# PKD.net
KiCad netlist of a schematic drawn in EAGLE
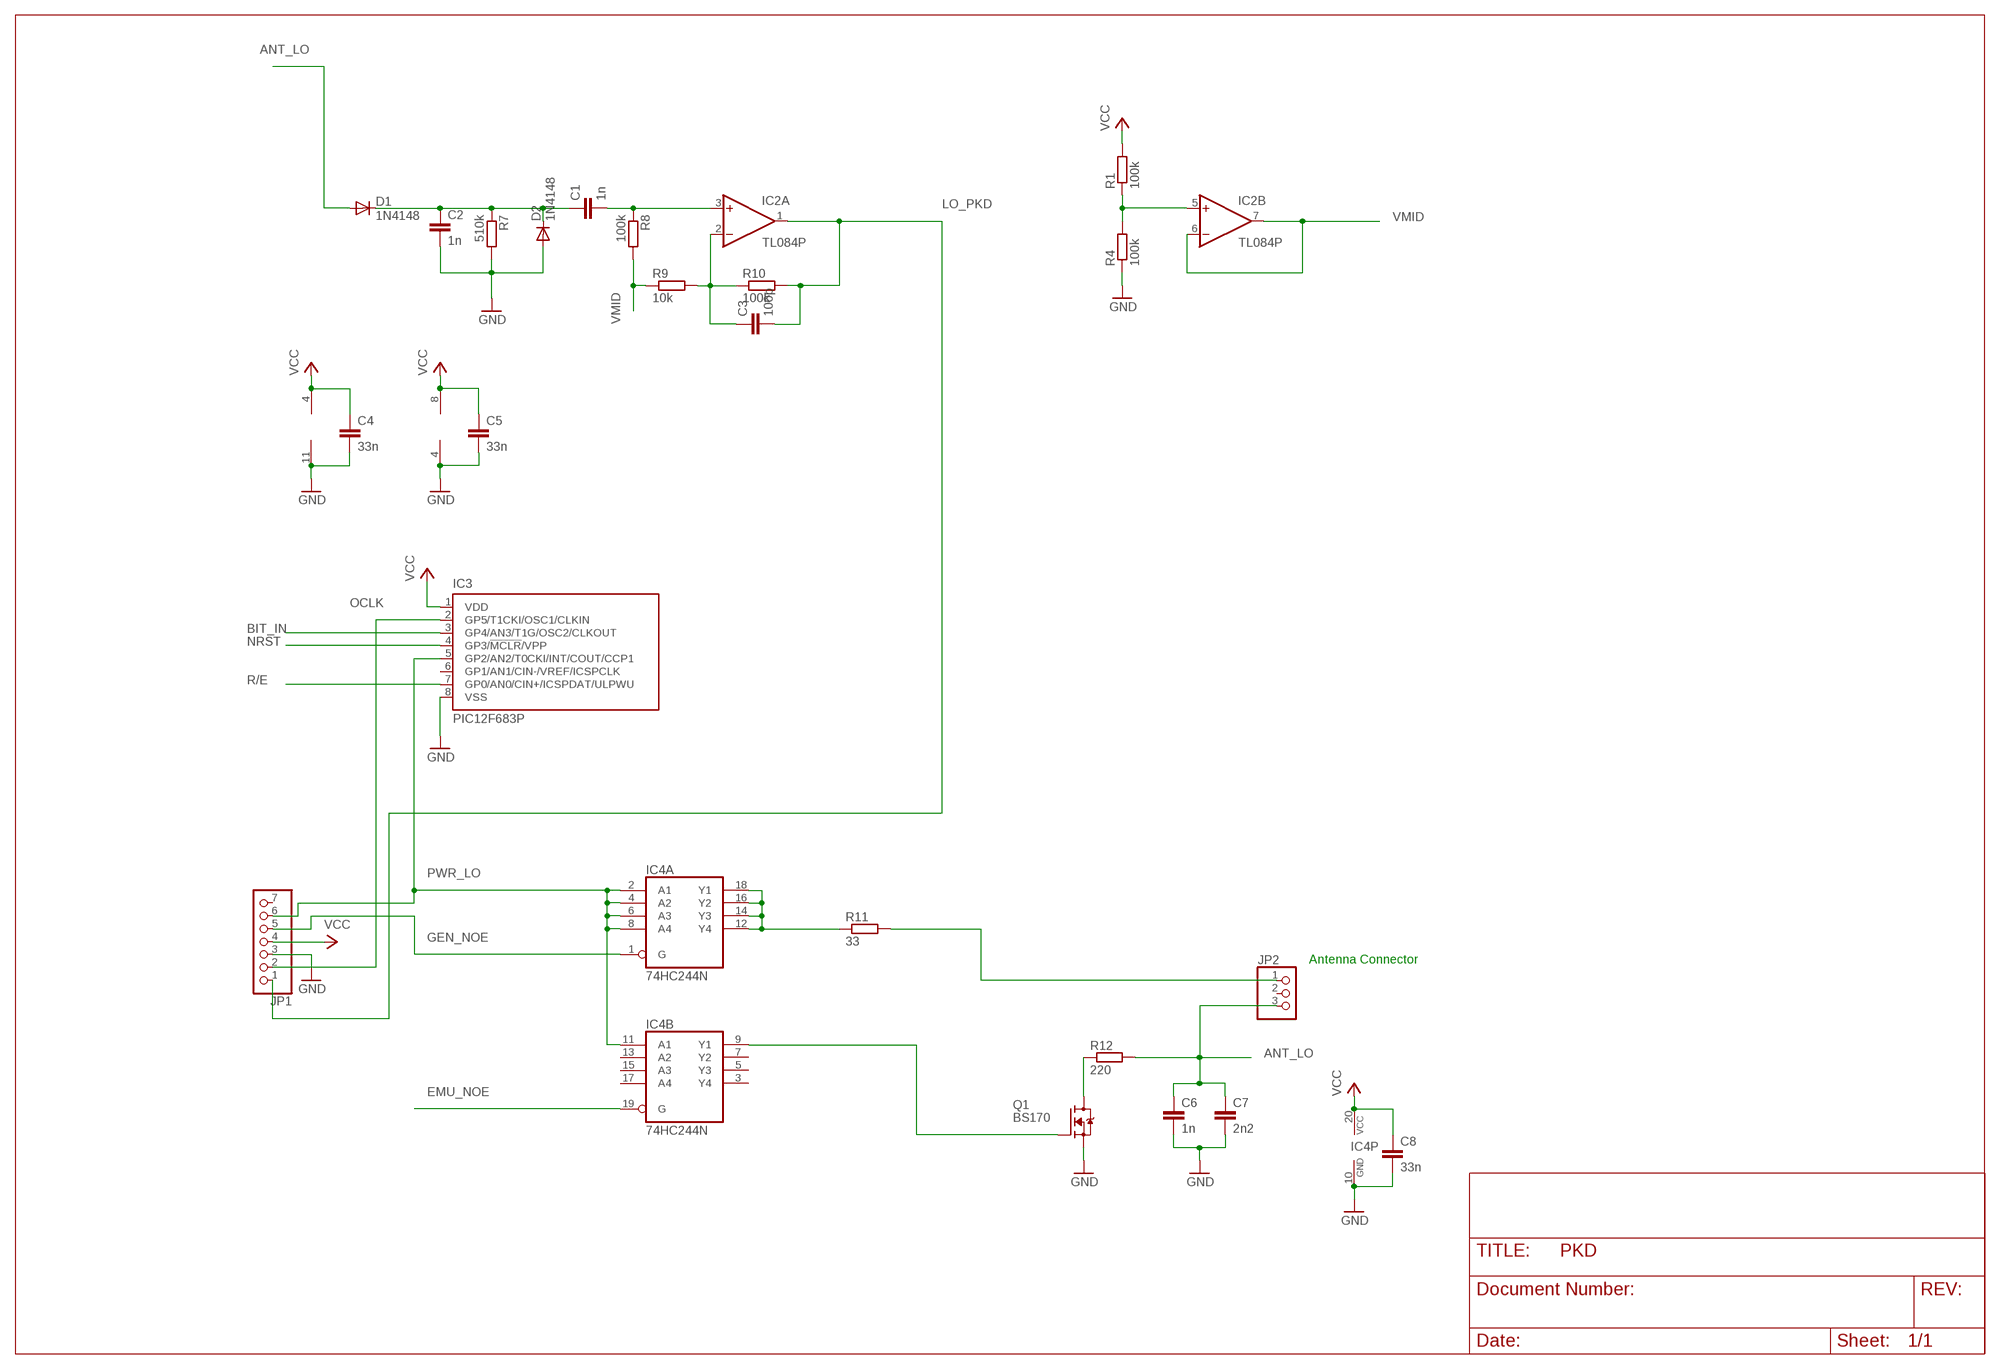
[diagram p0: schematic, sheet 1]

(export (version "E")
  (design (tool "Eeschema 10.0.6"))
  (components
    (comp (ref "C1")
      (value "1n")
      (footprint "eagle-import:C025-025X050")
      (libsource (lib "eagle-import") (part "C-EU025-025X050"))
    )
    (comp (ref "C2")
      (value "1n")
      (footprint "eagle-import:C050-030X075")
      (libsource (lib "eagle-import") (part "C-EU050-030X075"))
    )
    (comp (ref "C3")
      (value "100p")
      (footprint "eagle-import:C025-025X050")
      (libsource (lib "eagle-import") (part "C-EU025-025X050"))
    )
    (comp (ref "C4")
      (value "33n")
      (footprint "eagle-import:C025-025X050")
      (libsource (lib "eagle-import") (part "C-EU025-025X050"))
    )
    (comp (ref "C5")
      (value "33n")
      (footprint "eagle-import:C025-025X050")
      (libsource (lib "eagle-import") (part "C-EU025-025X050"))
    )
    (comp (ref "C6")
      (value "1n")
      (footprint "eagle-import:C025-025X050")
      (libsource (lib "eagle-import") (part "C-EU025-025X050"))
    )
    (comp (ref "C7")
      (value "2n2")
      (footprint "eagle-import:C025-025X050")
      (libsource (lib "eagle-import") (part "C-EU025-025X050"))
    )
    (comp (ref "C8")
      (value "33n")
      (footprint "eagle-import:C050-030X075")
      (libsource (lib "eagle-import") (part "C-EU050-030X075"))
    )
    (comp (ref "D1")
      (value "1N4148")
      (footprint "eagle-import:DO35-10")
      (libsource (lib "eagle-import") (part "1N4148DO35-10"))
    )
    (comp (ref "D2")
      (value "1N4148")
      (footprint "eagle-import:DO35-10")
      (libsource (lib "eagle-import") (part "1N4148DO35-10"))
    )
    (comp (ref "IC1")
      (value "LM393N")
      (footprint "eagle-import:DIL08")
      (libsource (lib "eagle-import") (part "LM393N"))
    )
    (comp (ref "IC2")
      (value "TL084P")
      (footprint "eagle-import:DIL14")
      (libsource (lib "eagle-import") (part "TL084P"))
    )
    (comp (ref "IC3")
      (value "PIC12F683P")
      (footprint "eagle-import:DIL8")
      (fields (field (name "MF") "MICROCHIP") (field (name "MPN") "PIC12F683-I/P"))
      (libsource (lib "eagle-import") (part "PIC12F683P"))
    )
    (comp (ref "IC4")
      (value "74HC244N")
      (footprint "eagle-import:DIL20")
      (libsource (lib "eagle-import") (part "74244NHC"))
    )
    (comp (ref "JP1")
      (value "PINHD-1X7")
      (footprint "eagle-import:1X07")
      (libsource (lib "eagle-import") (part "PINHD-1X7"))
    )
    (comp (ref "JP2")
      (value "PINHD-1X3/90")
      (footprint "eagle-import:1X03_90")
      (libsource (lib "eagle-import") (part "PINHD-1X3/90"))
    )
    (comp (ref "Q1")
      (value "BS170")
      (footprint "eagle-import:TO92-")
      (libsource (lib "eagle-import") (part "BS170"))
    )
    (comp (ref "R1")
      (value "100k")
      (footprint "eagle-import:0207_10")
      (libsource (lib "eagle-import") (part "R-EU_0207/10"))
    )
    (comp (ref "R4")
      (value "100k")
      (footprint "eagle-import:0207_10")
      (libsource (lib "eagle-import") (part "R-EU_0207/10"))
    )
    (comp (ref "R7")
      (value "510k")
      (footprint "eagle-import:0207_10")
      (libsource (lib "eagle-import") (part "R-EU_0207/10"))
    )
    (comp (ref "R8")
      (value "100k")
      (footprint "eagle-import:0207_10")
      (libsource (lib "eagle-import") (part "R-EU_0207/10"))
    )
    (comp (ref "R9")
      (value "10k")
      (footprint "eagle-import:0207_10")
      (libsource (lib "eagle-import") (part "R-EU_0207/10"))
    )
    (comp (ref "R10")
      (value "100k")
      (footprint "eagle-import:0207_10")
      (libsource (lib "eagle-import") (part "R-EU_0207/10"))
    )
    (comp (ref "R11")
      (value "33")
      (footprint "eagle-import:0207_10")
      (libsource (lib "eagle-import") (part "R-EU_0207/10"))
    )
    (comp (ref "R12")
      (value "220")
      (footprint "eagle-import:0207_10")
      (libsource (lib "eagle-import") (part "R-EU_0207/10"))
    )
  )
  (nets
    (net (code "1") (name "/ANT_LO") (class "Default")
      (node (ref "C6") (pin "1") (pinfunction "1_1") (pintype "passive"))
      (node (ref "C7") (pin "1") (pinfunction "1_1") (pintype "passive"))
      (node (ref "D1") (pin "A") (pinfunction "A_A") (pintype "passive"))
      (node (ref "JP2") (pin "3") (pinfunction "3_3") (pintype "passive"))
      (node (ref "R12") (pin "2") (pinfunction "2_2") (pintype "passive"))
    )
    (net (code "2") (name "/BIT_IN") (class "Default")
      (node (ref "IC3") (pin "3") (pinfunction "GP4/AN3/T1G/OSC2/CLKOUT_3") (pintype "bidirectional"))
    )
    (net (code "3") (name "/EMU_NOE") (class "Default")
      (node (ref "IC4") (pin "19") (pinfunction "G_19") (pintype "input"))
    )
    (net (code "4") (name "/GEN_NOE") (class "Default")
      (node (ref "IC4") (pin "1") (pinfunction "G_1") (pintype "input"))
      (node (ref "JP1") (pin "5") (pinfunction "5_5") (pintype "passive"))
    )
    (net (code "5") (name "/LO_PKD") (class "Default")
      (node (ref "C3") (pin "2") (pinfunction "2_2") (pintype "passive"))
      (node (ref "IC2") (pin "1") (pinfunction "OUT_1") (pintype "output"))
      (node (ref "JP1") (pin "1") (pinfunction "1_1") (pintype "passive"))
      (node (ref "R10") (pin "2") (pinfunction "2_2") (pintype "passive"))
    )
    (net (code "6") (name "/NRST") (class "Default")
      (node (ref "IC3") (pin "4") (pinfunction "GP3/~{MCLR}/VPP_4") (pintype "bidirectional"))
    )
    (net (code "7") (name "/OCLK") (class "Default")
      (node (ref "IC3") (pin "2") (pinfunction "GP5/T1CKI/OSC1/CLKIN_2") (pintype "bidirectional"))
      (node (ref "JP1") (pin "2") (pinfunction "2_2") (pintype "passive"))
    )
    (net (code "8") (name "/PWR_LO") (class "Default")
      (node (ref "IC3") (pin "5") (pinfunction "GP2/AN2/T0CKI/INT/COUT/CCP1_5") (pintype "bidirectional"))
      (node (ref "IC4") (pin "11") (pinfunction "A1_11") (pintype "input"))
      (node (ref "IC4") (pin "2") (pinfunction "A1_2") (pintype "input"))
      (node (ref "IC4") (pin "4") (pinfunction "A2_4") (pintype "input"))
      (node (ref "IC4") (pin "6") (pinfunction "A3_6") (pintype "input"))
      (node (ref "IC4") (pin "8") (pinfunction "A4_8") (pintype "input"))
      (node (ref "JP1") (pin "6") (pinfunction "6_6") (pintype "passive"))
    )
    (net (code "9") (name "/R{slash}E") (class "Default")
      (node (ref "IC3") (pin "7") (pinfunction "GP0/AN0/CIN+/ICSPDAT/ULPWU_7") (pintype "bidirectional"))
    )
    (net (code "10") (name "/VMID") (class "Default")
      (node (ref "IC2") (pin "6") (pinfunction "-IN_6") (pintype "input"))
      (node (ref "IC2") (pin "7") (pinfunction "OUT_7") (pintype "output"))
      (node (ref "R8") (pin "2") (pinfunction "2_2") (pintype "passive"))
      (node (ref "R9") (pin "1") (pinfunction "1_1") (pintype "passive"))
    )
    (net (code "11") (name "GND") (class "Default")
      (node (ref "C2") (pin "2") (pinfunction "2_2") (pintype "passive"))
      (node (ref "C4") (pin "2") (pinfunction "2_2") (pintype "passive"))
      (node (ref "C5") (pin "2") (pinfunction "2_2") (pintype "passive"))
      (node (ref "C6") (pin "2") (pinfunction "2_2") (pintype "passive"))
      (node (ref "C7") (pin "2") (pinfunction "2_2") (pintype "passive"))
      (node (ref "C8") (pin "2") (pinfunction "2_2") (pintype "passive"))
      (node (ref "D2") (pin "A") (pinfunction "A_A") (pintype "passive"))
      (node (ref "IC1") (pin "4") (pinfunction "V-_4") (pintype "power_in"))
      (node (ref "IC2") (pin "11") (pinfunction "V-_11") (pintype "power_in"))
      (node (ref "IC3") (pin "8") (pinfunction "VSS_8") (pintype "power_in"))
      (node (ref "IC4") (pin "10") (pinfunction "GND_10") (pintype "power_in"))
      (node (ref "JP1") (pin "3") (pinfunction "3_3") (pintype "passive"))
      (node (ref "Q1") (pin "3") (pinfunction "S_3") (pintype "passive"))
      (node (ref "R4") (pin "1") (pinfunction "1_1") (pintype "passive"))
      (node (ref "R7") (pin "2") (pinfunction "2_2") (pintype "passive"))
    )
    (net (code "12") (name "Net-(C1-Pad1)") (class "Default")
      (node (ref "C1") (pin "1") (pinfunction "1_1") (pintype "passive"))
      (node (ref "C2") (pin "1") (pinfunction "1_1") (pintype "passive"))
      (node (ref "D1") (pin "C") (pinfunction "C_C") (pintype "passive"))
      (node (ref "D2") (pin "C") (pinfunction "C_C") (pintype "passive"))
      (node (ref "R7") (pin "1") (pinfunction "1_1") (pintype "passive"))
    )
    (net (code "13") (name "Net-(IC2A-+IN)") (class "Default")
      (node (ref "C1") (pin "2") (pinfunction "2_2") (pintype "passive"))
      (node (ref "IC2") (pin "3") (pinfunction "+IN_3") (pintype "input"))
      (node (ref "R8") (pin "1") (pinfunction "1_1") (pintype "passive"))
    )
    (net (code "14") (name "Net-(IC2A--IN)") (class "Default")
      (node (ref "C3") (pin "1") (pinfunction "1_1") (pintype "passive"))
      (node (ref "IC2") (pin "2") (pinfunction "-IN_2") (pintype "input"))
      (node (ref "R10") (pin "1") (pinfunction "1_1") (pintype "passive"))
      (node (ref "R9") (pin "2") (pinfunction "2_2") (pintype "passive"))
    )
    (net (code "15") (name "Net-(IC2B-+IN)") (class "Default")
      (node (ref "IC2") (pin "5") (pinfunction "+IN_5") (pintype "input"))
      (node (ref "R1") (pin "1") (pinfunction "1_1") (pintype "passive"))
      (node (ref "R4") (pin "2") (pinfunction "2_2") (pintype "passive"))
    )
    (net (code "16") (name "Net-(IC4A-Y1)") (class "Default")
      (node (ref "IC4") (pin "12") (pinfunction "Y4_12") (pintype "tri_state"))
      (node (ref "IC4") (pin "14") (pinfunction "Y3_14") (pintype "tri_state"))
      (node (ref "IC4") (pin "16") (pinfunction "Y2_16") (pintype "tri_state"))
      (node (ref "IC4") (pin "18") (pinfunction "Y1_18") (pintype "tri_state"))
      (node (ref "R11") (pin "1") (pinfunction "1_1") (pintype "passive"))
    )
    (net (code "17") (name "Net-(IC4B-Y1)") (class "Default")
      (node (ref "IC4") (pin "9") (pinfunction "Y1_9") (pintype "tri_state"))
      (node (ref "Q1") (pin "2") (pinfunction "G_2") (pintype "passive"))
    )
    (net (code "18") (name "Net-(JP2-Pad1)") (class "Default")
      (node (ref "JP2") (pin "1") (pinfunction "1_1") (pintype "passive"))
      (node (ref "R11") (pin "2") (pinfunction "2_2") (pintype "passive"))
    )
    (net (code "19") (name "Net-(Q1-D)") (class "Default")
      (node (ref "Q1") (pin "1") (pinfunction "D_1") (pintype "passive"))
      (node (ref "R12") (pin "1") (pinfunction "1_1") (pintype "passive"))
    )
    (net (code "20") (name "VCC") (class "Default")
      (node (ref "C4") (pin "1") (pinfunction "1_1") (pintype "passive"))
      (node (ref "C5") (pin "1") (pinfunction "1_1") (pintype "passive"))
      (node (ref "C8") (pin "1") (pinfunction "1_1") (pintype "passive"))
      (node (ref "IC1") (pin "8") (pinfunction "V+_8") (pintype "power_in"))
      (node (ref "IC2") (pin "4") (pinfunction "V+_4") (pintype "power_in"))
      (node (ref "IC3") (pin "1") (pinfunction "VDD_1") (pintype "power_in"))
      (node (ref "IC4") (pin "20") (pinfunction "VCC_20") (pintype "power_in"))
      (node (ref "JP1") (pin "4") (pinfunction "4_4") (pintype "passive"))
      (node (ref "R1") (pin "2") (pinfunction "2_2") (pintype "passive"))
    )
    (net (code "21") (name "unconnected-(IC3-GP1{slash}AN1{slash}CIN-{slash}VREF{slash}ICSPCLK-Pad6)") (class "Default")
      (node (ref "IC3") (pin "6") (pinfunction "GP1/AN1/CIN-/VREF/ICSPCLK_6") (pintype "bidirectional"))
    )
    (net (code "22") (name "unconnected-(IC4B-A2-Pad13)") (class "Default")
      (node (ref "IC4") (pin "13") (pinfunction "A2_13") (pintype "input"))
    )
    (net (code "23") (name "unconnected-(IC4B-A3-Pad15)") (class "Default")
      (node (ref "IC4") (pin "15") (pinfunction "A3_15") (pintype "input"))
    )
    (net (code "24") (name "unconnected-(IC4B-A4-Pad17)") (class "Default")
      (node (ref "IC4") (pin "17") (pinfunction "A4_17") (pintype "input"))
    )
    (net (code "25") (name "unconnected-(IC4B-Y2-Pad7)") (class "Default")
      (node (ref "IC4") (pin "7") (pinfunction "Y2_7") (pintype "tri_state"))
    )
    (net (code "26") (name "unconnected-(IC4B-Y3-Pad5)") (class "Default")
      (node (ref "IC4") (pin "5") (pinfunction "Y3_5") (pintype "tri_state"))
    )
    (net (code "27") (name "unconnected-(IC4B-Y4-Pad3)") (class "Default")
      (node (ref "IC4") (pin "3") (pinfunction "Y4_3") (pintype "tri_state"))
    )
    (net (code "28") (name "unconnected-(JP1-Pad7)") (class "Default")
      (node (ref "JP1") (pin "7") (pinfunction "7_7") (pintype "passive"))
    )
    (net (code "29") (name "unconnected-(JP2-Pad2)") (class "Default")
      (node (ref "JP2") (pin "2") (pinfunction "2_2") (pintype "passive"))
    )
  )
)
